# ethernet.net
KiCad netlist of a schematic drawn in Altium Designer
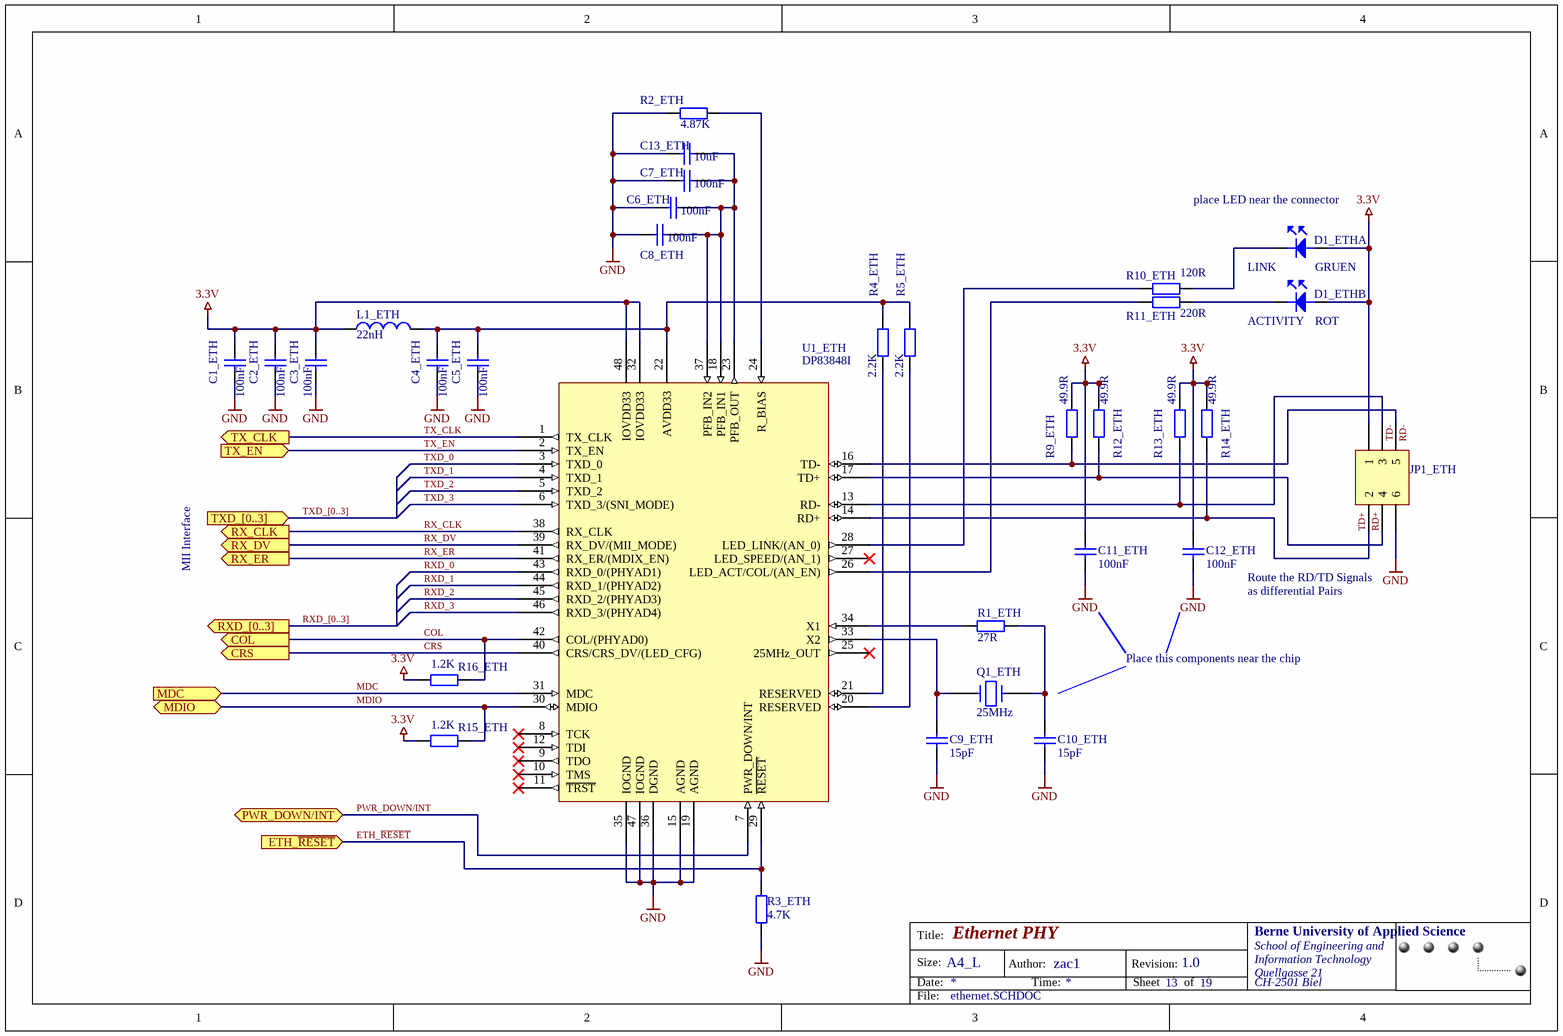
[diagram p0: ethernet.SCHDOC]

(export (version "E")
  (design (tool "Eeschema 10.0.6"))
  (components
    (comp (ref "C1_ETH")
      (value "100nF")
      (footprint "0402")
      (description "Capacitor")
      (fields
        (field (name "MANUFACTURER") "Murata")
        (field (name "PART NUMBER") "GRM155R71C104KA88D")
        (field (name "PUBLISHER") "Altium Limited")
      )
      (libsource (lib "Miscellaneous Devices") (part "Cap"))
    )
    (comp (ref "C2_ETH")
      (value "100nF")
      (footprint "0402")
      (description "Capacitor")
      (fields
        (field (name "MANUFACTURER") "Murata")
        (field (name "PART NUMBER") "GRM155R71C104KA88D")
        (field (name "PUBLISHER") "Altium Limited")
      )
      (libsource (lib "Miscellaneous Devices") (part "Cap"))
    )
    (comp (ref "C3_ETH")
      (value "100nF")
      (footprint "0402")
      (description "Capacitor")
      (fields
        (field (name "MANUFACTURER") "Murata")
        (field (name "PART NUMBER") "GRM155R71C104KA88D")
        (field (name "PUBLISHER") "Altium Limited")
      )
      (libsource (lib "Miscellaneous Devices") (part "Cap"))
    )
    (comp (ref "C4_ETH")
      (value "100nF")
      (footprint "0402")
      (description "Capacitor")
      (fields
        (field (name "MANUFACTURER") "Murata")
        (field (name "PART NUMBER") "GRM155R71C104KA88D")
        (field (name "PUBLISHER") "Altium Limited")
      )
      (libsource (lib "Miscellaneous Devices") (part "Cap"))
    )
    (comp (ref "C5_ETH")
      (value "100nF")
      (footprint "0402")
      (description "Capacitor")
      (fields
        (field (name "MANUFACTURER") "Murata")
        (field (name "PART NUMBER") "GRM155R71C104KA88D")
        (field (name "PUBLISHER") "Altium Limited")
      )
      (libsource (lib "Miscellaneous Devices") (part "Cap"))
    )
    (comp (ref "C6_ETH")
      (value "100nF")
      (footprint "0402")
      (description "Capacitor")
      (fields
        (field (name "MANUFACTURER") "Murata")
        (field (name "PART NUMBER") "GRM155R71C104KA88D")
        (field (name "PUBLISHER") "Altium Limited")
      )
      (libsource (lib "Miscellaneous Devices") (part "Cap"))
    )
    (comp (ref "C7_ETH")
      (value "100nF")
      (footprint "0402")
      (description "Capacitor")
      (fields
        (field (name "MANUFACTURER") "Murata")
        (field (name "PART NUMBER") "GRM155R71C104KA88D")
        (field (name "PUBLISHER") "Altium Limited")
      )
      (libsource (lib "Miscellaneous Devices") (part "Cap"))
    )
    (comp (ref "C8_ETH")
      (value "100nF")
      (footprint "0402")
      (description "Capacitor")
      (fields
        (field (name "MANUFACTURER") "Murata")
        (field (name "PART NUMBER") "GRM155R71C104KA88D")
        (field (name "PUBLISHER") "Altium Limited")
      )
      (libsource (lib "Miscellaneous Devices") (part "Cap"))
    )
    (comp (ref "C9_ETH")
      (value "15pF")
      (footprint "0402")
      (description "Capacitor")
      (fields
        (field (name "MANUFACTURER") "AVX")
        (field (name "PART NUMBER") "04025A150JAT2A")
        (field (name "PUBLISHER") "Altium Limited")
      )
      (libsource (lib "Miscellaneous Devices") (part "Cap"))
    )
    (comp (ref "C10_ETH")
      (value "15pF")
      (footprint "0402")
      (description "Capacitor")
      (fields
        (field (name "MANUFACTURER") "AVX")
        (field (name "PART NUMBER") "04025A150JAT2A")
        (field (name "PUBLISHER") "Altium Limited")
      )
      (libsource (lib "Miscellaneous Devices") (part "Cap"))
    )
    (comp (ref "C11_ETH")
      (value "100nF")
      (footprint "0402")
      (description "Capacitor")
      (fields
        (field (name "MANUFACTURER") "Murata")
        (field (name "PART NUMBER") "GRM155R71C104KA88D")
        (field (name "PUBLISHER") "Altium Limited")
      )
      (libsource (lib "Miscellaneous Devices") (part "Cap"))
    )
    (comp (ref "C12_ETH")
      (value "100nF")
      (footprint "0402")
      (description "Capacitor")
      (fields
        (field (name "MANUFACTURER") "Murata")
        (field (name "PART NUMBER") "GRM155R71C104KA88D")
        (field (name "PUBLISHER") "Altium Limited")
      )
      (libsource (lib "Miscellaneous Devices") (part "Cap"))
    )
    (comp (ref "C13_ETH")
      (value "10uF")
      (footprint "1206")
      (description "Capacitor")
      (fields
        (field (name "MANUFACTURER") "Murata")
        (field (name "PART NUMBER") "GRM31CR70J106KA01L")
        (field (name "PUBLISHER") "Altium Limited")
      )
      (libsource (lib "Miscellaneous Devices") (part "Cap"))
    )
    (comp (ref "D1_ETH")
      (value "1211C-LED")
      (footprint "stan-led4")
      (description "Stanley 1211C Bi-Color Ultra Compact SMT LED")
      (fields (field (name "MANUFACTURER") "Stanley") (field (name "PART NUMBER") "BRBG1211C"))
      (libsource (lib "gecko3-user") (part "1211C-LED"))
    )
    (comp (ref "JP1_ETH")
      (value "M22-2540305")
      (footprint "M22-2540305")
      (fields (field (name "MANUFACTURER") "HARWIN") (field (name "PART NUMBER") "M22F2040305"))
      (libsource (lib "gecko3-user") (part "M22-2540305"))
    )
    (comp (ref "L1_ETH")
      (value "22nH")
      (footprint "0603")
      (description "Inductor")
      (fields
        (field (name "MANUFACTURER") "Panasonic")
        (field (name "PART NUMBER") "ELJRE22NJFA")
        (field (name "PUBLISHER") "Altium Limited")
      )
      (libsource (lib "Miscellaneous Devices") (part "Inductor"))
    )
    (comp (ref "Q1_ETH")
      (value "25MHz")
      (footprint "AT49")
      (description "SMD Quarz in the AT49 Case, like the ABLS series from Abracon")
      (fields (field (name "MANUFACTURER") "ABRACON") (field (name "PART NUMBER") "ABLS-25.000MHZ-B2F-T"))
      (libsource (lib "gecko3-user") (part "QUARZ-SMD"))
    )
    (comp (ref "R1_ETH")
      (value "27R")
      (footprint "0402")
      (description "Resistor")
      (fields
        (field (name "MANUFACTURER") "PHYCOMP")
        (field (name "PART NUMBER") "232270672709")
        (field (name "PUBLISHER") "Altium Limited")
      )
      (libsource (lib "") (part "Res2_2"))
    )
    (comp (ref "R2_ETH")
      (value "4.87K")
      (footprint "0603")
      (description "Resistor")
      (fields
        (field (name "MANUFACTURER") "Multicomp")
        (field (name "PART NUMBER") "MC 0.063W 0603 1% 4K87")
        (field (name "PUBLISHER") "Altium Limited")
      )
      (libsource (lib "") (part "Res2_1"))
    )
    (comp (ref "R3_ETH")
      (value "4.7K")
      (footprint "0402")
      (description "Resistor")
      (fields
        (field (name "MANUFACTURER") "PHYCOMP")
        (field (name "PART NUMBER") "232270674702")
        (field (name "PUBLISHER") "Altium Limited")
      )
      (libsource (lib "Miscellaneous Devices") (part "Res2"))
    )
    (comp (ref "R4_ETH")
      (value "2.2K")
      (footprint "0402")
      (description "Resistor")
      (fields
        (field (name "MANUFACTURER") "PHYCOMP")
        (field (name "PART NUMBER") "232270672202")
        (field (name "PUBLISHER") "Altium Limited")
      )
      (libsource (lib "Miscellaneous Devices") (part "Res2"))
    )
    (comp (ref "R5_ETH")
      (value "2.2K")
      (footprint "0402")
      (description "Resistor")
      (fields
        (field (name "MANUFACTURER") "PHYCOMP")
        (field (name "PART NUMBER") "232270672202")
        (field (name "PUBLISHER") "Altium Limited")
      )
      (libsource (lib "Miscellaneous Devices") (part "Res2"))
    )
    (comp (ref "R9_ETH")
      (value "49.9R")
      (footprint "0603")
      (description "Resistor")
      (fields
        (field (name "MANUFACTURER") "Multicomp")
        (field (name "PART NUMBER") "MC 0.063W 0603 1% 49R9")
        (field (name "PUBLISHER") "Altium Limited")
      )
      (libsource (lib "Miscellaneous Devices") (part "Res2"))
    )
    (comp (ref "R10_ETH")
      (value "120R")
      (footprint "0402")
      (description "Resistor")
      (fields
        (field (name "MANUFACTURER") "PHYCOMP")
        (field (name "PART NUMBER") "232270671201")
        (field (name "PUBLISHER") "Altium Limited")
      )
      (libsource (lib "") (part "Res2_2"))
    )
    (comp (ref "R11_ETH")
      (value "220R")
      (footprint "0402")
      (description "Resistor")
      (fields
        (field (name "MANUFACTURER") "PHYCOMP")
        (field (name "PART NUMBER") "232270672201")
        (field (name "PUBLISHER") "Altium Limited")
      )
      (libsource (lib "") (part "Res2_2"))
    )
    (comp (ref "R12_ETH")
      (value "49.9R")
      (footprint "0603")
      (description "Resistor")
      (fields
        (field (name "MANUFACTURER") "Multicomp")
        (field (name "PART NUMBER") "MC 0.063W 0603 1% 49R9")
        (field (name "PUBLISHER") "Altium Limited")
      )
      (libsource (lib "Miscellaneous Devices") (part "Res2"))
    )
    (comp (ref "R13_ETH")
      (value "49.9R")
      (footprint "0603")
      (description "Resistor")
      (fields
        (field (name "MANUFACTURER") "Multicomp")
        (field (name "PART NUMBER") "MC 0.063W 0603 1% 49R9")
        (field (name "PUBLISHER") "Altium Limited")
      )
      (libsource (lib "Miscellaneous Devices") (part "Res2"))
    )
    (comp (ref "R14_ETH")
      (value "49.9R")
      (footprint "0603")
      (description "Resistor")
      (fields
        (field (name "MANUFACTURER") "Multicomp")
        (field (name "PART NUMBER") "MC 0.063W 0603 1% 49R9")
        (field (name "PUBLISHER") "Altium Limited")
      )
      (libsource (lib "Miscellaneous Devices") (part "Res2"))
    )
    (comp (ref "R15_ETH")
      (value "1.2K")
      (footprint "0402")
      (description "Resistor")
      (fields
        (field (name "MANUFACTURER") "PHYCOMP")
        (field (name "PART NUMBER") "232270671202")
        (field (name "PUBLISHER") "Altium Limited")
      )
      (libsource (lib "") (part "Res2_1"))
    )
    (comp (ref "R16_ETH")
      (value "1.2K")
      (footprint "0402")
      (description "Resistor")
      (fields
        (field (name "MANUFACTURER") "PHYCOMP")
        (field (name "PART NUMBER") "232270671202")
        (field (name "PUBLISHER") "Altium Limited")
      )
      (libsource (lib "") (part "Res2_1"))
    )
    (comp (ref "U1_ETH")
      (value "DP83848I")
      (footprint "F-QFP7X7-G48/N")
      (description "Single Port 10/100 Mb/s Ethernet Physical Layer Transceiver")
      (fields (field (name "MANUFACTURER") "National") (field (name "PART NUMBER") "DP83848IVV/NOPB"))
      (libsource (lib "gecko3-user") (part "DP83848I"))
    )
  )
  (nets
    (net (code "1") (name "/COL") (class "Default")
      (node (ref "R16_ETH") (pin "2") (pinfunction "2_2") (pintype "passive"))
      (node (ref "U1_ETH") (pin "42") (pinfunction "COL/(PHYAD0)_42") (pintype "output"))
    )
    (net (code "2") (name "/CRS") (class "Default")
      (node (ref "U1_ETH") (pin "40") (pinfunction "CRS/CRS_DV/(LED_CFG)_40") (pintype "output"))
    )
    (net (code "3") (name "/ETH_~{RESET}") (class "Default")
      (node (ref "R3_ETH") (pin "2") (pinfunction "2_2") (pintype "passive"))
      (node (ref "U1_ETH") (pin "29") (pinfunction "~{RESET}_29") (pintype "input"))
    )
    (net (code "4") (name "/MDC") (class "Default")
      (node (ref "U1_ETH") (pin "31") (pinfunction "MDC_31") (pintype "input"))
    )
    (net (code "5") (name "/MDIO") (class "Default")
      (node (ref "R15_ETH") (pin "2") (pinfunction "2_2") (pintype "passive"))
      (node (ref "U1_ETH") (pin "30") (pinfunction "MDIO_30") (pintype "bidirectional"))
    )
    (net (code "6") (name "/PWR_DOWN{slash}INT") (class "Default")
      (node (ref "U1_ETH") (pin "7") (pinfunction "PWR_DOWN/INT_7") (pintype "input"))
    )
    (net (code "7") (name "/RD+") (class "Default")
      (node (ref "JP1_ETH") (pin "4") (pinfunction "4_4") (pintype "passive"))
      (node (ref "R12_ETH") (pin "1") (pinfunction "1_1") (pintype "passive"))
      (node (ref "U1_ETH") (pin "17") (pinfunction "TD+_17") (pintype "bidirectional"))
    )
    (net (code "8") (name "/RD-") (class "Default")
      (node (ref "JP1_ETH") (pin "5") (pinfunction "5_5") (pintype "passive"))
      (node (ref "R9_ETH") (pin "1") (pinfunction "1_1") (pintype "passive"))
      (node (ref "U1_ETH") (pin "16") (pinfunction "TD-_16") (pintype "bidirectional"))
    )
    (net (code "9") (name "/RXD_0") (class "Default")
      (node (ref "U1_ETH") (pin "43") (pinfunction "RXD_0/(PHYAD1)_43") (pintype "output"))
    )
    (net (code "10") (name "/RXD_1") (class "Default")
      (node (ref "U1_ETH") (pin "44") (pinfunction "RXD_1/(PHYAD2)_44") (pintype "output"))
    )
    (net (code "11") (name "/RXD_2") (class "Default")
      (node (ref "U1_ETH") (pin "45") (pinfunction "RXD_2/(PHYAD3)_45") (pintype "output"))
    )
    (net (code "12") (name "/RXD_3") (class "Default")
      (node (ref "U1_ETH") (pin "46") (pinfunction "RXD_3/(PHYAD4)_46") (pintype "output"))
    )
    (net (code "14") (name "/RX_CLK") (class "Default")
      (node (ref "U1_ETH") (pin "38") (pinfunction "RX_CLK_38") (pintype "output"))
    )
    (net (code "15") (name "/RX_DV") (class "Default")
      (node (ref "U1_ETH") (pin "39") (pinfunction "RX_DV/(MII_MODE)_39") (pintype "output"))
    )
    (net (code "16") (name "/RX_ER") (class "Default")
      (node (ref "U1_ETH") (pin "41") (pinfunction "RX_ER/(MDIX_EN)_41") (pintype "output"))
    )
    (net (code "17") (name "/TD+") (class "Default")
      (node (ref "JP1_ETH") (pin "2") (pinfunction "2_2") (pintype "passive"))
      (node (ref "R14_ETH") (pin "1") (pinfunction "1_1") (pintype "passive"))
      (node (ref "U1_ETH") (pin "14") (pinfunction "RD+_14") (pintype "bidirectional"))
    )
    (net (code "18") (name "/TD-") (class "Default")
      (node (ref "JP1_ETH") (pin "3") (pinfunction "3_3") (pintype "passive"))
      (node (ref "R13_ETH") (pin "1") (pinfunction "1_1") (pintype "passive"))
      (node (ref "U1_ETH") (pin "13") (pinfunction "RD-_13") (pintype "bidirectional"))
    )
    (net (code "19") (name "/TXD_0") (class "Default")
      (node (ref "U1_ETH") (pin "3") (pinfunction "TXD_0_3") (pintype "input"))
    )
    (net (code "20") (name "/TXD_1") (class "Default")
      (node (ref "U1_ETH") (pin "4") (pinfunction "TXD_1_4") (pintype "input"))
    )
    (net (code "21") (name "/TXD_2") (class "Default")
      (node (ref "U1_ETH") (pin "5") (pinfunction "TXD_2_5") (pintype "input"))
    )
    (net (code "22") (name "/TXD_3") (class "Default")
      (node (ref "U1_ETH") (pin "6") (pinfunction "TXD_3/(SNI_MODE)_6") (pintype "input"))
    )
    (net (code "24") (name "/TX_CLK") (class "Default")
      (node (ref "U1_ETH") (pin "1") (pinfunction "TX_CLK_1") (pintype "output"))
    )
    (net (code "25") (name "/TX_EN") (class "Default")
      (node (ref "U1_ETH") (pin "2") (pinfunction "TX_EN_2") (pintype "input"))
    )
    (net (code "26") (name "3.3V") (class "Default")
      (node (ref "C11_ETH") (pin "2") (pinfunction "2_2") (pintype "passive"))
      (node (ref "C12_ETH") (pin "2") (pinfunction "2_2") (pintype "passive"))
      (node (ref "C1_ETH") (pin "2") (pinfunction "2_2") (pintype "passive"))
      (node (ref "C2_ETH") (pin "2") (pinfunction "2_2") (pintype "passive"))
      (node (ref "C3_ETH") (pin "2") (pinfunction "2_2") (pintype "passive"))
      (node (ref "D1_ETH") (pin "1") (pinfunction "A_1") (pintype "passive"))
      (node (ref "D1_ETH") (pin "3") (pinfunction "A_3") (pintype "passive"))
      (node (ref "JP1_ETH") (pin "1") (pinfunction "1_1") (pintype "passive"))
      (node (ref "L1_ETH") (pin "1") (pinfunction "1_1") (pintype "passive"))
      (node (ref "R12_ETH") (pin "2") (pinfunction "2_2") (pintype "passive"))
      (node (ref "R13_ETH") (pin "2") (pinfunction "2_2") (pintype "passive"))
      (node (ref "R14_ETH") (pin "2") (pinfunction "2_2") (pintype "passive"))
      (node (ref "R15_ETH") (pin "1") (pinfunction "1_1") (pintype "passive"))
      (node (ref "R16_ETH") (pin "1") (pinfunction "1_1") (pintype "passive"))
      (node (ref "R9_ETH") (pin "2") (pinfunction "2_2") (pintype "passive"))
      (node (ref "U1_ETH") (pin "32") (pinfunction "IOVDD33_32") (pintype "power_in"))
      (node (ref "U1_ETH") (pin "48") (pinfunction "IOVDD33_48") (pintype "power_in"))
    )
    (net (code "27") (name "GND") (class "Default")
      (node (ref "C10_ETH") (pin "1") (pinfunction "1_1") (pintype "passive"))
      (node (ref "C11_ETH") (pin "1") (pinfunction "1_1") (pintype "passive"))
      (node (ref "C12_ETH") (pin "1") (pinfunction "1_1") (pintype "passive"))
      (node (ref "C13_ETH") (pin "1") (pinfunction "1_1") (pintype "passive"))
      (node (ref "C1_ETH") (pin "1") (pinfunction "1_1") (pintype "passive"))
      (node (ref "C2_ETH") (pin "1") (pinfunction "1_1") (pintype "passive"))
      (node (ref "C3_ETH") (pin "1") (pinfunction "1_1") (pintype "passive"))
      (node (ref "C4_ETH") (pin "1") (pinfunction "1_1") (pintype "passive"))
      (node (ref "C5_ETH") (pin "1") (pinfunction "1_1") (pintype "passive"))
      (node (ref "C6_ETH") (pin "1") (pinfunction "1_1") (pintype "passive"))
      (node (ref "C7_ETH") (pin "1") (pinfunction "1_1") (pintype "passive"))
      (node (ref "C8_ETH") (pin "1") (pinfunction "1_1") (pintype "passive"))
      (node (ref "C9_ETH") (pin "1") (pinfunction "1_1") (pintype "passive"))
      (node (ref "JP1_ETH") (pin "6") (pinfunction "6_6") (pintype "passive"))
      (node (ref "R2_ETH") (pin "1") (pinfunction "1_1") (pintype "passive"))
      (node (ref "R3_ETH") (pin "1") (pinfunction "1_1") (pintype "passive"))
      (node (ref "U1_ETH") (pin "15") (pinfunction "AGND_15") (pintype "power_in"))
      (node (ref "U1_ETH") (pin "19") (pinfunction "AGND_19") (pintype "power_in"))
      (node (ref "U1_ETH") (pin "35") (pinfunction "IOGND_35") (pintype "power_in"))
      (node (ref "U1_ETH") (pin "36") (pinfunction "DGND_36") (pintype "power_in"))
      (node (ref "U1_ETH") (pin "47") (pinfunction "IOGND_47") (pintype "power_in"))
    )
    (net (code "28") (name "Net-(C10_ETH-Pad2)") (class "Default")
      (node (ref "C10_ETH") (pin "2") (pinfunction "2_2") (pintype "passive"))
      (node (ref "Q1_ETH") (pin "2") (pinfunction "2_2") (pintype "passive"))
      (node (ref "R1_ETH") (pin "1") (pinfunction "1_1") (pintype "passive"))
    )
    (net (code "29") (name "Net-(D1_ETHA-K)") (class "Default")
      (node (ref "D1_ETH") (pin "4") (pinfunction "K_4") (pintype "passive"))
      (node (ref "R10_ETH") (pin "1") (pinfunction "1_1") (pintype "passive"))
    )
    (net (code "30") (name "Net-(D1_ETHB-K)") (class "Default")
      (node (ref "D1_ETH") (pin "2") (pinfunction "K_2") (pintype "passive"))
      (node (ref "R11_ETH") (pin "1") (pinfunction "1_1") (pintype "passive"))
    )
    (net (code "31") (name "Net-(R4_ETH-Pad1)") (class "Default")
      (node (ref "R4_ETH") (pin "1") (pinfunction "1_1") (pintype "passive"))
      (node (ref "U1_ETH") (pin "21") (pinfunction "RESERVED_21") (pintype "bidirectional"))
    )
    (net (code "32") (name "Net-(R5_ETH-Pad1)") (class "Default")
      (node (ref "R5_ETH") (pin "1") (pinfunction "1_1") (pintype "passive"))
      (node (ref "U1_ETH") (pin "20") (pinfunction "RESERVED_20") (pintype "bidirectional"))
    )
    (net (code "33") (name "Net-(U1_ETH-AVDD33)") (class "Default")
      (node (ref "C4_ETH") (pin "2") (pinfunction "2_2") (pintype "passive"))
      (node (ref "C5_ETH") (pin "2") (pinfunction "2_2") (pintype "passive"))
      (node (ref "L1_ETH") (pin "2") (pinfunction "2_2") (pintype "passive"))
      (node (ref "R4_ETH") (pin "2") (pinfunction "2_2") (pintype "passive"))
      (node (ref "R5_ETH") (pin "2") (pinfunction "2_2") (pintype "passive"))
      (node (ref "U1_ETH") (pin "22") (pinfunction "AVDD33_22") (pintype "power_in"))
    )
    (net (code "34") (name "Net-(U1_ETH-LED_ACT{slash}COL{slash}(AN_EN))") (class "Default")
      (node (ref "R11_ETH") (pin "2") (pinfunction "2_2") (pintype "passive"))
      (node (ref "U1_ETH") (pin "26") (pinfunction "LED_ACT/COL/(AN_EN)_26") (pintype "output"))
    )
    (net (code "35") (name "Net-(U1_ETH-LED_LINK{slash}(AN_0))") (class "Default")
      (node (ref "R10_ETH") (pin "2") (pinfunction "2_2") (pintype "passive"))
      (node (ref "U1_ETH") (pin "28") (pinfunction "LED_LINK/(AN_0)_28") (pintype "output"))
    )
    (net (code "36") (name "Net-(U1_ETH-PFB_IN1)") (class "Default")
      (node (ref "C13_ETH") (pin "2") (pinfunction "2_2") (pintype "passive"))
      (node (ref "C6_ETH") (pin "2") (pinfunction "2_2") (pintype "passive"))
      (node (ref "C7_ETH") (pin "2") (pinfunction "2_2") (pintype "passive"))
      (node (ref "C8_ETH") (pin "2") (pinfunction "2_2") (pintype "passive"))
      (node (ref "U1_ETH") (pin "18") (pinfunction "PFB_IN1_18") (pintype "input"))
      (node (ref "U1_ETH") (pin "23") (pinfunction "PFB_OUT_23") (pintype "output"))
      (node (ref "U1_ETH") (pin "37") (pinfunction "PFB_IN2_37") (pintype "input"))
    )
    (net (code "37") (name "Net-(U1_ETH-R_BIAS)") (class "Default")
      (node (ref "R2_ETH") (pin "2") (pinfunction "2_2") (pintype "passive"))
      (node (ref "U1_ETH") (pin "24") (pinfunction "R_BIAS_24") (pintype "input"))
    )
    (net (code "38") (name "Net-(U1_ETH-X1)") (class "Default")
      (node (ref "R1_ETH") (pin "2") (pinfunction "2_2") (pintype "passive"))
      (node (ref "U1_ETH") (pin "34") (pinfunction "X1_34") (pintype "input"))
    )
    (net (code "39") (name "Net-(U1_ETH-X2)") (class "Default")
      (node (ref "C9_ETH") (pin "2") (pinfunction "2_2") (pintype "passive"))
      (node (ref "Q1_ETH") (pin "1") (pinfunction "1_1") (pintype "passive"))
      (node (ref "U1_ETH") (pin "33") (pinfunction "X2_33") (pintype "output"))
    )
    (net (code "40") (name "unconnected-(U1_ETH-25MHz_OUT-Pad25)") (class "Default")
      (node (ref "U1_ETH") (pin "25") (pinfunction "25MHz_OUT_25") (pintype "output+no_connect"))
    )
    (net (code "41") (name "unconnected-(U1_ETH-LED_SPEED{slash}(AN_1)-Pad27)") (class "Default")
      (node (ref "U1_ETH") (pin "27") (pinfunction "LED_SPEED/(AN_1)_27") (pintype "output+no_connect"))
    )
    (net (code "42") (name "unconnected-(U1_ETH-TCK-Pad8)") (class "Default")
      (node (ref "U1_ETH") (pin "8") (pinfunction "TCK_8") (pintype "input+no_connect"))
    )
    (net (code "43") (name "unconnected-(U1_ETH-TDI-Pad12)") (class "Default")
      (node (ref "U1_ETH") (pin "12") (pinfunction "TDI_12") (pintype "input+no_connect"))
    )
    (net (code "44") (name "unconnected-(U1_ETH-TDO-Pad9)") (class "Default")
      (node (ref "U1_ETH") (pin "9") (pinfunction "TDO_9") (pintype "output+no_connect"))
    )
    (net (code "45") (name "unconnected-(U1_ETH-TMS-Pad10)") (class "Default")
      (node (ref "U1_ETH") (pin "10") (pinfunction "TMS_10") (pintype "input+no_connect"))
    )
    (net (code "46") (name "unconnected-(U1_ETH-~{TRST}-Pad11)") (class "Default")
      (node (ref "U1_ETH") (pin "11") (pinfunction "~{TRST}_11") (pintype "output+no_connect"))
    )
  )
)
